# Alarm_Sch_1.net
KiCad netlist of a schematic drawn in Altium Designer
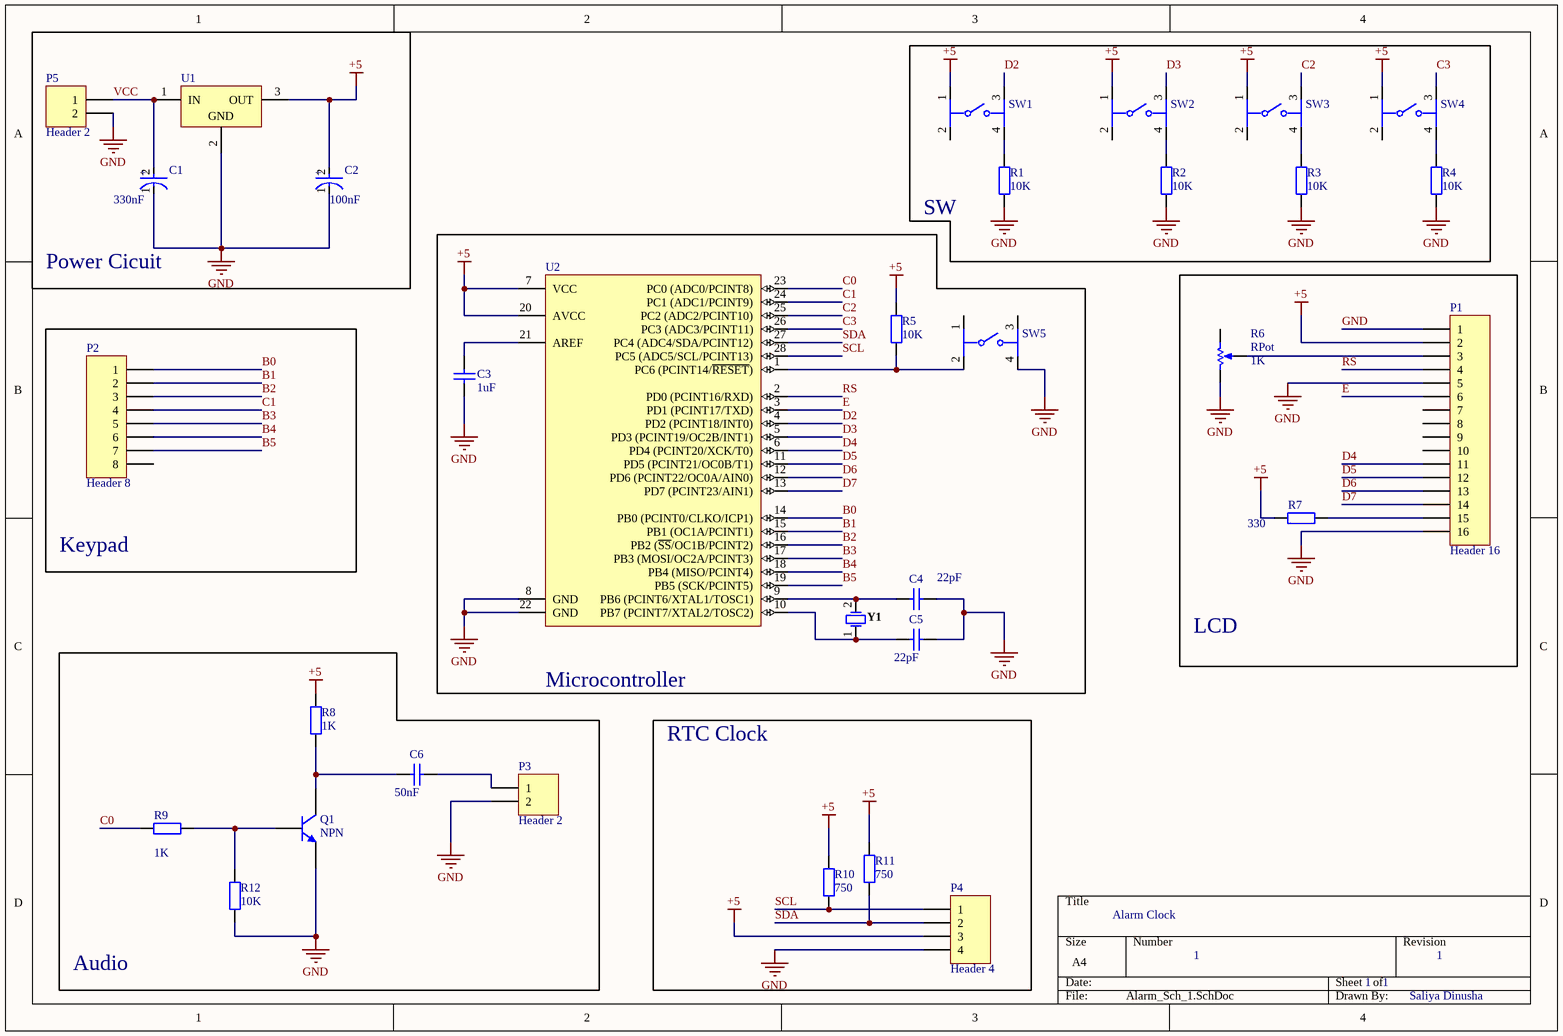
[diagram p0: Alarm_Sch_1.SchDoc]

(export (version "E")
  (design (tool "Eeschema 10.0.6"))
  (components
    (comp (ref "C1")
      (value "UVR2AR22MDD1TD")
      (footprint "FP-UVR2AR22MDD1TD-MFG")
      (description "CAP ALUM 0.22UF 20% 100V RADIAL")
      (fields (field (name "TOLERANCE") "20%") (field (name "CAPACITANCE") "330nF"))
      (libsource (lib "Altium Content Vault") (part "cf48714ba7e38822c1575c7ec0b6d1f"))
    )
    (comp (ref "C2")
      (value "UVR2AR22MDD1TD")
      (footprint "FP-UVR2AR22MDD1TD-MFG")
      (description "CAP ALUM 0.22UF 20% 100V RADIAL")
      (fields (field (name "TOLERANCE") "20%") (field (name "CAPACITANCE") "100nF"))
      (libsource (lib "Altium Content Vault") (part "cf48714ba7e38822c1575c7ec0b6d1f"))
    )
    (comp (ref "C3")
      (value "1uF")
      (footprint "KEMT-C315-THT-2")
      (description "Capacitor, Ceramic, 0.01 uF, +/- 10%, 100 V, X7R, -55 to 125 degC, 2-Pin THD, RoHS, Bulk")
      (fields (field (name "Comment") "C315C103K1R5TA"))
      (libsource (lib "Altium Content Vault") (part "CAP-NP-2"))
    )
    (comp (ref "C4")
      (value "22pF")
      (footprint "KEMT-C315-THT-2")
      (description "Capacitor, Ceramic, 0.01 uF, +/- 10%, 100 V, X7R, -55 to 125 degC, 2-Pin THD, RoHS, Bulk")
      (fields (field (name "Comment") "C315C103K1R5TA"))
      (libsource (lib "Altium Content Vault") (part "CAP-NP-2"))
    )
    (comp (ref "C5")
      (value "22pF")
      (footprint "KEMT-C315-THT-2")
      (description "Capacitor, Ceramic, 0.01 uF, +/- 10%, 100 V, X7R, -55 to 125 degC, 2-Pin THD, RoHS, Bulk")
      (fields (field (name "Comment") "C315C103K1R5TA"))
      (libsource (lib "Altium Content Vault") (part "CAP-NP-2"))
    )
    (comp (ref "C6")
      (value "50nF")
      (footprint "KEMT-C315-THT-2")
      (description "Capacitor, Ceramic, 0.01 uF, +/- 10%, 100 V, X7R, -55 to 125 degC, 2-Pin THD, RoHS, Bulk")
      (fields (field (name "Comment") "C315C103K1R5TA"))
      (libsource (lib "Altium Content Vault") (part "CAP-NP-2"))
    )
    (comp (ref "P1")
      (value "Header 16")
      (footprint "HDR1X16")
      (description "Header, 16-Pin")
      (fields (field (name "PUBLISHER") "Altium Limited"))
      (libsource (lib "Miscellaneous Connectors") (part "Header 16"))
    )
    (comp (ref "P2")
      (value "Header 8")
      (footprint "HDR1X8")
      (description "Header, 8-Pin")
      (fields (field (name "PUBLISHER") "Altium Limited"))
      (libsource (lib "Miscellaneous Connectors") (part "Header 8"))
    )
    (comp (ref "P3")
      (value "Header 2")
      (footprint "HDR1X2")
      (description "Header, 2-Pin")
      (fields (field (name "PUBLISHER") "Altium Limited"))
      (libsource (lib "") (part "Header 2_1"))
    )
    (comp (ref "P4")
      (value "Header 4")
      (footprint "HDR1X4")
      (description "Header, 4-Pin")
      (fields (field (name "PUBLISHER") "Altium Limited"))
      (libsource (lib "Miscellaneous Connectors") (part "Header 4"))
    )
    (comp (ref "P5")
      (value "Header 2")
      (footprint "HDR1X2")
      (description "Header, 2-Pin")
      (fields (field (name "PUBLISHER") "Altium Limited"))
      (libsource (lib "Miscellaneous Connectors") (part "Header 2"))
    )
    (comp (ref "Q1")
      (value "NPN")
      (footprint "TO-226-AA")
      (description "NPN Bipolar Transistor")
      (fields (field (name "PUBLISHER") "Altium Limited"))
      (libsource (lib "Miscellaneous Devices") (part "NPN"))
    )
    (comp (ref "R1")
      (value "10K")
      (footprint "AXIAL-0.4")
      (description "Resistor")
      (fields (field (name "Comment") "Res2") (field (name "PUBLISHER") "Altium Limited"))
      (libsource (lib "") (part "Res2_1"))
    )
    (comp (ref "R2")
      (value "10K")
      (footprint "AXIAL-0.4")
      (description "Resistor")
      (fields (field (name "Comment") "Res2") (field (name "PUBLISHER") "Altium Limited"))
      (libsource (lib "") (part "Res2_1"))
    )
    (comp (ref "R3")
      (value "10K")
      (footprint "AXIAL-0.4")
      (description "Resistor")
      (fields (field (name "Comment") "Res2") (field (name "PUBLISHER") "Altium Limited"))
      (libsource (lib "") (part "Res2_1"))
    )
    (comp (ref "R4")
      (value "10K")
      (footprint "AXIAL-0.4")
      (description "Resistor")
      (fields (field (name "Comment") "Res2") (field (name "PUBLISHER") "Altium Limited"))
      (libsource (lib "") (part "Res2_1"))
    )
    (comp (ref "R5")
      (value "10K")
      (footprint "AXIAL-0.4")
      (description "Resistor")
      (fields (field (name "Comment") "Res2") (field (name "PUBLISHER") "Altium Limited"))
      (libsource (lib "") (part "Res2_1"))
    )
    (comp (ref "R6")
      (value "RPot")
      (footprint "VR5")
      (description "Potentiometer")
      (fields (field (name "ALTIUM_VALUE") "1K") (field (name "PUBLISHER") "Altium Limited"))
      (libsource (lib "Miscellaneous Devices") (part "RPot"))
    )
    (comp (ref "R7")
      (value "330")
      (footprint "AXIAL-0.4")
      (description "Resistor")
      (fields (field (name "Comment") "Res2") (field (name "PUBLISHER") "Altium Limited"))
      (libsource (lib "Miscellaneous Devices") (part "Res2"))
    )
    (comp (ref "R8")
      (value "1K")
      (footprint "AXIAL-0.4")
      (description "Resistor")
      (fields (field (name "Comment") "Res2") (field (name "PUBLISHER") "Altium Limited"))
      (libsource (lib "") (part "Res2_1"))
    )
    (comp (ref "R9")
      (value "1K")
      (footprint "AXIAL-0.4")
      (description "Resistor")
      (fields (field (name "Comment") "Res2") (field (name "PUBLISHER") "Altium Limited"))
      (libsource (lib "Miscellaneous Devices") (part "Res2"))
    )
    (comp (ref "R10")
      (value "750")
      (footprint "AXIAL-0.4")
      (description "Resistor")
      (fields (field (name "Comment") "Res2") (field (name "PUBLISHER") "Altium Limited"))
      (libsource (lib "") (part "Res2_1"))
    )
    (comp (ref "R11")
      (value "750")
      (footprint "AXIAL-0.4")
      (description "Resistor")
      (fields (field (name "Comment") "Res2") (field (name "PUBLISHER") "Altium Limited"))
      (libsource (lib "") (part "Res2_1"))
    )
    (comp (ref "R12")
      (value "10K")
      (footprint "AXIAL-0.4")
      (description "Resistor")
      (fields (field (name "Comment") "Res2") (field (name "PUBLISHER") "Altium Limited"))
      (libsource (lib "") (part "Res2_1"))
    )
    (comp (ref "SW1")
      (value "1-1825910-0")
      (footprint "FP-1-1825910-0-MFG")
      (description "SWITCH TACTILE SPST-NO 0.05A 24V")
      (libsource (lib "Altium Content Vault") (part "b8895f3f4cefb76e1819d2863dba89b"))
    )
    (comp (ref "SW2")
      (value "1-1825910-0")
      (footprint "FP-1-1825910-0-MFG")
      (description "SWITCH TACTILE SPST-NO 0.05A 24V")
      (libsource (lib "Altium Content Vault") (part "b8895f3f4cefb76e1819d2863dba89b"))
    )
    (comp (ref "SW3")
      (value "1-1825910-0")
      (footprint "FP-1-1825910-0-MFG")
      (description "SWITCH TACTILE SPST-NO 0.05A 24V")
      (libsource (lib "Altium Content Vault") (part "b8895f3f4cefb76e1819d2863dba89b"))
    )
    (comp (ref "SW4")
      (value "1-1825910-0")
      (footprint "FP-1-1825910-0-MFG")
      (description "SWITCH TACTILE SPST-NO 0.05A 24V")
      (libsource (lib "Altium Content Vault") (part "b8895f3f4cefb76e1819d2863dba89b"))
    )
    (comp (ref "SW5")
      (value "1-1825910-0")
      (footprint "FP-1-1825910-0-MFG")
      (description "SWITCH TACTILE SPST-NO 0.05A 24V")
      (libsource (lib "Altium Content Vault") (part "b8895f3f4cefb76e1819d2863dba89b"))
    )
    (comp (ref "U1")
      (value "L7805CV")
      (footprint "TO220")
      (description "Positive Voltage Regulator, 5V, 3-Pin TO-220")
      (libsource (lib "Altium Content Vault") (part "PM-REG-L4940-SIL3"))
    )
    (comp (ref "U2")
      (value "ATmega328-PU")
      (footprint "28P3")
      (libsource (lib "Altium Content Vault") (part "MC-8B-ATM48-IL28"))
    )
    (comp (ref "Y1")
      (value "FOXSLF/160-20")
      (footprint "FOX-FOXSLF160-20")
      (description "Resistance Weld Thru-Hole Crystal, 16 MHz, -20 to 70 degC, 2-Pin THD, RoHS, Bulk")
      (fields (field (name "TOLERANCE") "1%"))
      (libsource (lib "Altium Content Vault") (part "XTAL-1-2-2"))
    )
  )
  (nets
    (net (code "1") (name "+5") (class "Default")
      (node (ref "C2") (pin "2") (pinfunction "A_2") (pintype "passive"))
      (node (ref "P1") (pin "2") (pinfunction "2_2") (pintype "passive"))
      (node (ref "P4") (pin "3") (pinfunction "3_3") (pintype "passive"))
      (node (ref "R10") (pin "2") (pinfunction "2_2") (pintype "passive"))
      (node (ref "R11") (pin "2") (pinfunction "2_2") (pintype "passive"))
      (node (ref "R5") (pin "2") (pinfunction "2_2") (pintype "passive"))
      (node (ref "R7") (pin "1") (pinfunction "1_1") (pintype "passive"))
      (node (ref "R8") (pin "2") (pinfunction "2_2") (pintype "passive"))
      (node (ref "SW1") (pin "1") (pinfunction "1_1") (pintype "passive"))
      (node (ref "SW2") (pin "1") (pinfunction "1_1") (pintype "passive"))
      (node (ref "SW3") (pin "1") (pinfunction "1_1") (pintype "passive"))
      (node (ref "SW4") (pin "1") (pinfunction "1_1") (pintype "passive"))
      (node (ref "U1") (pin "3") (pinfunction "OUT_3") (pintype "power_in"))
      (node (ref "U2") (pin "20") (pinfunction "AVCC_20") (pintype "power_in"))
      (node (ref "U2") (pin "7") (pinfunction "VCC_7") (pintype "power_in"))
    )
    (net (code "2") (name "/B0") (class "Default")
      (node (ref "P2") (pin "1") (pinfunction "1_1") (pintype "passive"))
      (node (ref "U2") (pin "14") (pinfunction "PB0_(PCINT0/CLKO/ICP1)_14") (pintype "bidirectional"))
    )
    (net (code "3") (name "/B1") (class "Default")
      (node (ref "P2") (pin "2") (pinfunction "2_2") (pintype "passive"))
      (node (ref "U2") (pin "15") (pinfunction "PB1_(OC1A/PCINT1)_15") (pintype "bidirectional"))
    )
    (net (code "4") (name "/B2") (class "Default")
      (node (ref "P2") (pin "3") (pinfunction "3_3") (pintype "passive"))
      (node (ref "U2") (pin "16") (pinfunction "PB2_(~{SS}/OC1B/PCINT2)_16") (pintype "bidirectional"))
    )
    (net (code "5") (name "/B3") (class "Default")
      (node (ref "P2") (pin "5") (pinfunction "5_5") (pintype "passive"))
      (node (ref "U2") (pin "17") (pinfunction "PB3_(MOSI/OC2A/PCINT3)_17") (pintype "bidirectional"))
    )
    (net (code "6") (name "/B4") (class "Default")
      (node (ref "P2") (pin "6") (pinfunction "6_6") (pintype "passive"))
      (node (ref "U2") (pin "18") (pinfunction "PB4_(MISO/PCINT4)_18") (pintype "bidirectional"))
    )
    (net (code "7") (name "/B5") (class "Default")
      (node (ref "P2") (pin "7") (pinfunction "7_7") (pintype "passive"))
      (node (ref "U2") (pin "19") (pinfunction "PB5_(SCK/PCINT5)_19") (pintype "bidirectional"))
    )
    (net (code "8") (name "/C0") (class "Default")
      (node (ref "R9") (pin "1") (pinfunction "1_1") (pintype "passive"))
      (node (ref "U2") (pin "23") (pinfunction "PC0_(ADC0/PCINT8)_23") (pintype "bidirectional"))
    )
    (net (code "9") (name "/C1") (class "Default")
      (node (ref "P2") (pin "4") (pinfunction "4_4") (pintype "passive"))
      (node (ref "U2") (pin "24") (pinfunction "PC1_(ADC1/PCINT9)_24") (pintype "bidirectional"))
    )
    (net (code "10") (name "/C2") (class "Default")
      (node (ref "SW3") (pin "3") (pinfunction "3_3") (pintype "passive"))
      (node (ref "U2") (pin "25") (pinfunction "PC2_(ADC2/PCINT10)_25") (pintype "bidirectional"))
    )
    (net (code "11") (name "/C3") (class "Default")
      (node (ref "SW4") (pin "3") (pinfunction "3_3") (pintype "passive"))
      (node (ref "U2") (pin "26") (pinfunction "PC3_(ADC3/PCINT11)_26") (pintype "bidirectional"))
    )
    (net (code "12") (name "/D2") (class "Default")
      (node (ref "SW1") (pin "3") (pinfunction "3_3") (pintype "passive"))
      (node (ref "U2") (pin "4") (pinfunction "PD2_(PCINT18/INT0)_4") (pintype "bidirectional"))
    )
    (net (code "13") (name "/D3") (class "Default")
      (node (ref "SW2") (pin "3") (pinfunction "3_3") (pintype "passive"))
      (node (ref "U2") (pin "5") (pinfunction "PD3_(PCINT19/OC2B/INT1)_5") (pintype "bidirectional"))
    )
    (net (code "14") (name "/D4") (class "Default")
      (node (ref "P1") (pin "11") (pinfunction "11_11") (pintype "passive"))
      (node (ref "U2") (pin "6") (pinfunction "PD4_(PCINT20/XCK/T0)_6") (pintype "bidirectional"))
    )
    (net (code "15") (name "/D5") (class "Default")
      (node (ref "P1") (pin "12") (pinfunction "12_12") (pintype "passive"))
      (node (ref "U2") (pin "11") (pinfunction "PD5_(PCINT21/OC0B/T1)_11") (pintype "bidirectional"))
    )
    (net (code "16") (name "/D6") (class "Default")
      (node (ref "P1") (pin "13") (pinfunction "13_13") (pintype "passive"))
      (node (ref "U2") (pin "12") (pinfunction "PD6_(PCINT22/OC0A/AIN0)_12") (pintype "bidirectional"))
    )
    (net (code "17") (name "/D7") (class "Default")
      (node (ref "P1") (pin "14") (pinfunction "14_14") (pintype "passive"))
      (node (ref "U2") (pin "13") (pinfunction "PD7_(PCINT23/AIN1)_13") (pintype "bidirectional"))
    )
    (net (code "18") (name "/E") (class "Default")
      (node (ref "P1") (pin "6") (pinfunction "6_6") (pintype "passive"))
      (node (ref "U2") (pin "3") (pinfunction "PD1_(PCINT17/TXD)_3") (pintype "bidirectional"))
    )
    (net (code "19") (name "/RS") (class "Default")
      (node (ref "P1") (pin "4") (pinfunction "4_4") (pintype "passive"))
      (node (ref "U2") (pin "2") (pinfunction "PD0_(PCINT16/RXD)_2") (pintype "bidirectional"))
    )
    (net (code "20") (name "/SCL") (class "Default")
      (node (ref "P4") (pin "1") (pinfunction "1_1") (pintype "passive"))
      (node (ref "R10") (pin "1") (pinfunction "1_1") (pintype "passive"))
      (node (ref "U2") (pin "28") (pinfunction "PC5_(ADC5/SCL/PCINT13)_28") (pintype "bidirectional"))
    )
    (net (code "21") (name "/SDA") (class "Default")
      (node (ref "P4") (pin "2") (pinfunction "2_2") (pintype "passive"))
      (node (ref "R11") (pin "1") (pinfunction "1_1") (pintype "passive"))
      (node (ref "U2") (pin "27") (pinfunction "PC4_(ADC4/SDA/PCINT12)_27") (pintype "bidirectional"))
    )
    (net (code "22") (name "/VCC") (class "Default")
      (node (ref "C1") (pin "2") (pinfunction "A_2") (pintype "passive"))
      (node (ref "P5") (pin "1") (pinfunction "1_1") (pintype "passive"))
      (node (ref "U1") (pin "1") (pinfunction "IN_1") (pintype "power_in"))
    )
    (net (code "23") (name "GND") (class "Default")
      (node (ref "C1") (pin "1") (pinfunction "C_1") (pintype "passive"))
      (node (ref "C2") (pin "1") (pinfunction "C_1") (pintype "passive"))
      (node (ref "C3") (pin "1") (pinfunction "1_1") (pintype "passive"))
      (node (ref "C4") (pin "2") (pinfunction "2_2") (pintype "passive"))
      (node (ref "C5") (pin "2") (pinfunction "2_2") (pintype "passive"))
      (node (ref "P1") (pin "1") (pinfunction "1_1") (pintype "passive"))
      (node (ref "P1") (pin "16") (pinfunction "16_16") (pintype "passive"))
      (node (ref "P1") (pin "5") (pinfunction "5_5") (pintype "passive"))
      (node (ref "P3") (pin "2") (pinfunction "2_2") (pintype "passive"))
      (node (ref "P4") (pin "4") (pinfunction "4_4") (pintype "passive"))
      (node (ref "P5") (pin "2") (pinfunction "2_2") (pintype "passive"))
      (node (ref "Q1") (pin "3") (pinfunction "E_3") (pintype "passive"))
      (node (ref "R1") (pin "1") (pinfunction "1_1") (pintype "passive"))
      (node (ref "R12") (pin "1") (pinfunction "1_1") (pintype "passive"))
      (node (ref "R2") (pin "1") (pinfunction "1_1") (pintype "passive"))
      (node (ref "R3") (pin "1") (pinfunction "1_1") (pintype "passive"))
      (node (ref "R4") (pin "1") (pinfunction "1_1") (pintype "passive"))
      (node (ref "R6") (pin "2") (pinfunction "BOT_2") (pintype "passive"))
      (node (ref "SW5") (pin "4") (pinfunction "4_4") (pintype "passive"))
      (node (ref "U1") (pin "2") (pinfunction "GND_2") (pintype "power_in"))
      (node (ref "U2") (pin "22") (pinfunction "GND_22") (pintype "power_in"))
      (node (ref "U2") (pin "8") (pinfunction "GND_8") (pintype "power_in"))
    )
    (net (code "24") (name "Net-(C6-Pad2)") (class "Default")
      (node (ref "C6") (pin "2") (pinfunction "2_2") (pintype "passive"))
      (node (ref "P3") (pin "1") (pinfunction "1_1") (pintype "passive"))
    )
    (net (code "25") (name "Net-(P1-Pad15)") (class "Default")
      (node (ref "P1") (pin "15") (pinfunction "15_15") (pintype "passive"))
      (node (ref "R7") (pin "2") (pinfunction "2_2") (pintype "passive"))
    )
    (net (code "26") (name "Net-(Q1-B)") (class "Default")
      (node (ref "Q1") (pin "2") (pinfunction "B_2") (pintype "passive"))
      (node (ref "R12") (pin "2") (pinfunction "2_2") (pintype "passive"))
      (node (ref "R9") (pin "2") (pinfunction "2_2") (pintype "passive"))
    )
    (net (code "27") (name "Net-(Q1-C)") (class "Default")
      (node (ref "C6") (pin "1") (pinfunction "1_1") (pintype "passive"))
      (node (ref "Q1") (pin "1") (pinfunction "C_1") (pintype "passive"))
      (node (ref "R8") (pin "1") (pinfunction "1_1") (pintype "passive"))
    )
    (net (code "28") (name "Net-(R1-Pad2)") (class "Default")
      (node (ref "R1") (pin "2") (pinfunction "2_2") (pintype "passive"))
      (node (ref "SW1") (pin "4") (pinfunction "4_4") (pintype "passive"))
    )
    (net (code "29") (name "Net-(R2-Pad2)") (class "Default")
      (node (ref "R2") (pin "2") (pinfunction "2_2") (pintype "passive"))
      (node (ref "SW2") (pin "4") (pinfunction "4_4") (pintype "passive"))
    )
    (net (code "30") (name "Net-(R3-Pad2)") (class "Default")
      (node (ref "R3") (pin "2") (pinfunction "2_2") (pintype "passive"))
      (node (ref "SW3") (pin "4") (pinfunction "4_4") (pintype "passive"))
    )
    (net (code "31") (name "Net-(R4-Pad2)") (class "Default")
      (node (ref "R4") (pin "2") (pinfunction "2_2") (pintype "passive"))
      (node (ref "SW4") (pin "4") (pinfunction "4_4") (pintype "passive"))
    )
    (net (code "32") (name "Net-(R6-TAP)") (class "Default")
      (node (ref "P1") (pin "3") (pinfunction "3_3") (pintype "passive"))
      (node (ref "R6") (pin "3") (pinfunction "TAP_3") (pintype "passive"))
    )
    (net (code "33") (name "Net-(U2-AREF)") (class "Default")
      (node (ref "C3") (pin "2") (pinfunction "2_2") (pintype "passive"))
      (node (ref "U2") (pin "21") (pinfunction "AREF_21") (pintype "power_in"))
    )
    (net (code "34") (name "Net-(U2-PB6_(PCINT6{slash}XTAL1{slash}TOSC1))") (class "Default")
      (node (ref "C4") (pin "1") (pinfunction "1_1") (pintype "passive"))
      (node (ref "U2") (pin "9") (pinfunction "PB6_(PCINT6/XTAL1/TOSC1)_9") (pintype "bidirectional"))
      (node (ref "Y1") (pin "2") (pinfunction "2_2") (pintype "passive"))
    )
    (net (code "35") (name "Net-(U2-PB7_(PCINT7{slash}XTAL2{slash}TOSC2))") (class "Default")
      (node (ref "C5") (pin "1") (pinfunction "1_1") (pintype "passive"))
      (node (ref "U2") (pin "10") (pinfunction "PB7_(PCINT7/XTAL2/TOSC2)_10") (pintype "bidirectional"))
      (node (ref "Y1") (pin "1") (pinfunction "1_1") (pintype "passive"))
    )
    (net (code "36") (name "Net-(U2-PC6_(PCINT14{slash}~{RESET}))") (class "Default")
      (node (ref "R5") (pin "1") (pinfunction "1_1") (pintype "passive"))
      (node (ref "SW5") (pin "2") (pinfunction "2_2") (pintype "passive"))
      (node (ref "U2") (pin "1") (pinfunction "PC6_(PCINT14/~{RESET})_1") (pintype "bidirectional"))
    )
    (net (code "37") (name "unconnected-(P1-Pad7)") (class "Default")
      (node (ref "P1") (pin "7") (pinfunction "7_7") (pintype "passive"))
    )
    (net (code "38") (name "unconnected-(P1-Pad8)") (class "Default")
      (node (ref "P1") (pin "8") (pinfunction "8_8") (pintype "passive"))
    )
    (net (code "39") (name "unconnected-(P1-Pad9)") (class "Default")
      (node (ref "P1") (pin "9") (pinfunction "9_9") (pintype "passive"))
    )
    (net (code "40") (name "unconnected-(P1-Pad10)") (class "Default")
      (node (ref "P1") (pin "10") (pinfunction "10_10") (pintype "passive"))
    )
    (net (code "41") (name "unconnected-(P2-Pad8)") (class "Default")
      (node (ref "P2") (pin "8") (pinfunction "8_8") (pintype "passive"))
    )
    (net (code "42") (name "unconnected-(R6-TOP-Pad1)") (class "Default")
      (node (ref "R6") (pin "1") (pinfunction "TOP_1") (pintype "passive"))
    )
    (net (code "43") (name "unconnected-(SW1-Pad2)") (class "Default")
      (node (ref "SW1") (pin "2") (pinfunction "2_2") (pintype "passive"))
    )
    (net (code "44") (name "unconnected-(SW2-Pad2)") (class "Default")
      (node (ref "SW2") (pin "2") (pinfunction "2_2") (pintype "passive"))
    )
    (net (code "45") (name "unconnected-(SW3-Pad2)") (class "Default")
      (node (ref "SW3") (pin "2") (pinfunction "2_2") (pintype "passive"))
    )
    (net (code "46") (name "unconnected-(SW4-Pad2)") (class "Default")
      (node (ref "SW4") (pin "2") (pinfunction "2_2") (pintype "passive"))
    )
    (net (code "47") (name "unconnected-(SW5-Pad1)") (class "Default")
      (node (ref "SW5") (pin "1") (pinfunction "1_1") (pintype "passive"))
    )
    (net (code "48") (name "unconnected-(SW5-Pad3)") (class "Default")
      (node (ref "SW5") (pin "3") (pinfunction "3_3") (pintype "passive"))
    )
  )
)
